# brd-relays3-draft2.net
KiCad netlist of a schematic drawn in EAGLE
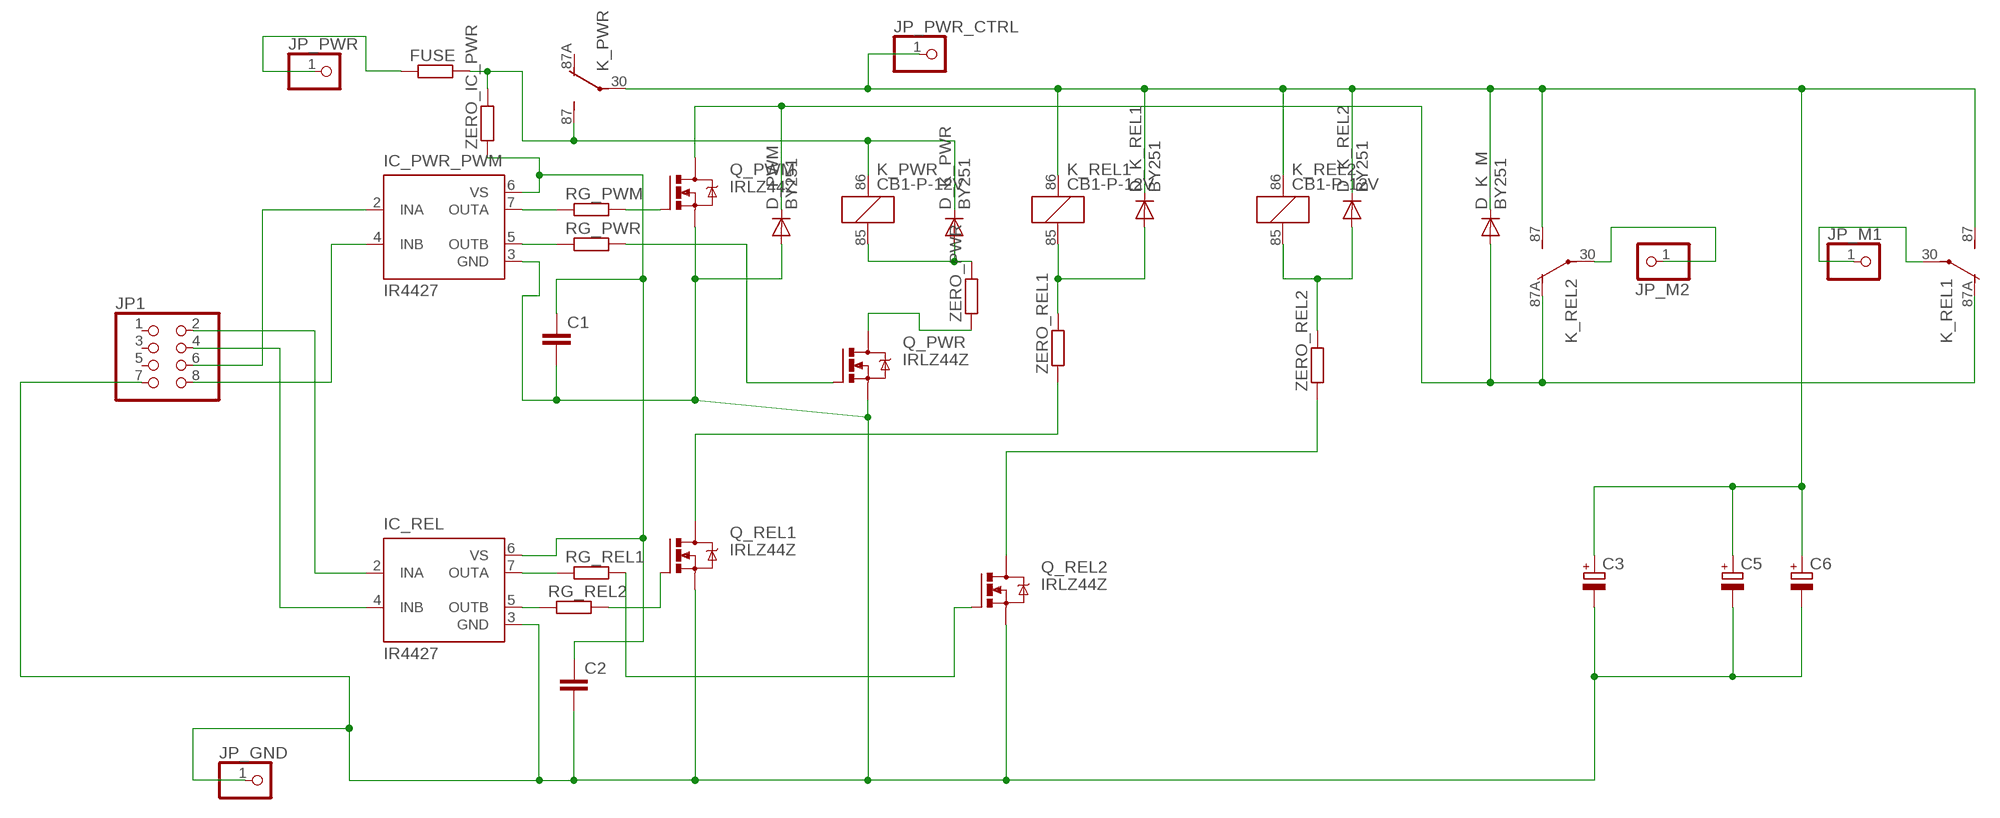
[diagram p0: schematic, sheet 1]

(export (version "E")
  (design (tool "Eeschema 10.0.6"))
  (components
    (comp (ref "C1")
      (value "C-EU050-055X075")
      (footprint "eagle-import:C050-055X075")
      (libsource (lib "eagle-import") (part "C-EU050-055X075"))
    )
    (comp (ref "C2")
      (value "C-EU050-055X075")
      (footprint "eagle-import:C050-055X075")
      (libsource (lib "eagle-import") (part "C-EU050-055X075"))
    )
    (comp (ref "C3")
      (value "CPOL-EUE5-13")
      (footprint "eagle-import:E5-13")
      (libsource (lib "eagle-import") (part "CPOL-EUE5-13"))
    )
    (comp (ref "C5")
      (value "CPOL-EUE5-13")
      (footprint "eagle-import:E5-13")
      (libsource (lib "eagle-import") (part "CPOL-EUE5-13"))
    )
    (comp (ref "C6")
      (value "CPOL-EUE5-13")
      (footprint "eagle-import:E5-13")
      (libsource (lib "eagle-import") (part "CPOL-EUE5-13"))
    )
    (comp (ref "D_K_M")
      (value "BY251")
      (footprint "eagle-import:DO201-15")
      (libsource (lib "eagle-import") (part "BY251"))
    )
    (comp (ref "D_K_PWR")
      (value "BY251")
      (footprint "eagle-import:DO201-15")
      (libsource (lib "eagle-import") (part "BY251"))
    )
    (comp (ref "D_K_REL1")
      (value "BY251")
      (footprint "eagle-import:DO201-15")
      (libsource (lib "eagle-import") (part "BY251"))
    )
    (comp (ref "D_K_REL2")
      (value "BY251")
      (footprint "eagle-import:DO201-15")
      (libsource (lib "eagle-import") (part "BY251"))
    )
    (comp (ref "D_PWM")
      (value "BY251")
      (footprint "eagle-import:DO201-15")
      (libsource (lib "eagle-import") (part "BY251"))
    )
    (comp (ref "FUSE")
      (value "R-EU_0207/10")
      (footprint "eagle-import:FUSE_PACK1")
      (libsource (lib "eagle-import") (part "R-EU_0207/10"))
    )
    (comp (ref "IC_PWR_PWM")
      (value "IR4427")
      (footprint "eagle-import:DIL08")
      (fields (field (name "MF") "INTERNATIONAL RECTIFIER(IR)"))
      (libsource (lib "eagle-import") (part "IR4427"))
    )
    (comp (ref "IC_REL")
      (value "IR4427")
      (footprint "eagle-import:DIL08")
      (fields (field (name "MF") "INTERNATIONAL RECTIFIER(IR)"))
      (libsource (lib "eagle-import") (part "IR4427"))
    )
    (comp (ref "JP1")
      (value "PINHD-2X4")
      (footprint "eagle-import:2X04")
      (libsource (lib "eagle-import") (part "PINHD-2X4"))
    )
    (comp (ref "JP_GND")
      (value "PINHD-1X1")
      (footprint "eagle-import:1X01")
      (libsource (lib "eagle-import") (part "PINHD-1X1"))
    )
    (comp (ref "JP_M1")
      (value "PINHD-1X1")
      (footprint "eagle-import:1X01")
      (libsource (lib "eagle-import") (part "PINHD-1X1"))
    )
    (comp (ref "JP_M2")
      (value "PINHD-1X1")
      (footprint "eagle-import:1X01")
      (libsource (lib "eagle-import") (part "PINHD-1X1"))
    )
    (comp (ref "JP_PWR")
      (value "PINHD-1X1")
      (footprint "eagle-import:1X01")
      (libsource (lib "eagle-import") (part "PINHD-1X1"))
    )
    (comp (ref "JP_PWR_CTRL")
      (value "PINHD-1X1")
      (footprint "eagle-import:1X01")
      (libsource (lib "eagle-import") (part "PINHD-1X1"))
    )
    (comp (ref "K_PWR")
      (value "CB1-P-12V")
      (footprint "eagle-import:CB1")
      (fields (field (name "MF") "AROMAT/ MATSUSHITA"))
      (libsource (lib "eagle-import") (part "CB1-P-12V"))
    )
    (comp (ref "K_REL1")
      (value "CB1-P-12V")
      (footprint "eagle-import:CB1")
      (fields (field (name "MF") "AROMAT/ MATSUSHITA"))
      (libsource (lib "eagle-import") (part "CB1-P-12V"))
    )
    (comp (ref "K_REL2")
      (value "CB1-P-12V")
      (footprint "eagle-import:CB1")
      (fields (field (name "MF") "AROMAT/ MATSUSHITA"))
      (libsource (lib "eagle-import") (part "CB1-P-12V"))
    )
    (comp (ref "Q_PWM")
      (value "IRLZ44Z")
      (footprint "eagle-import:TO220BH")
      (libsource (lib "eagle-import") (part "IRLZ44Z"))
    )
    (comp (ref "Q_PWR")
      (value "IRLZ44Z")
      (footprint "eagle-import:TO220BH")
      (libsource (lib "eagle-import") (part "IRLZ44Z"))
    )
    (comp (ref "Q_REL1")
      (value "IRLZ44Z")
      (footprint "eagle-import:TO220BH")
      (libsource (lib "eagle-import") (part "IRLZ44Z"))
    )
    (comp (ref "Q_REL2")
      (value "IRLZ44Z")
      (footprint "eagle-import:TO220BH")
      (libsource (lib "eagle-import") (part "IRLZ44Z"))
    )
    (comp (ref "RG_PWM")
      (value "R-EU_0207/10")
      (footprint "eagle-import:0207_10")
      (libsource (lib "eagle-import") (part "rcl_R-EU_0207/10"))
    )
    (comp (ref "RG_PWR")
      (value "R-EU_0207/10")
      (footprint "eagle-import:0207_10")
      (libsource (lib "eagle-import") (part "rcl_R-EU_0207/10"))
    )
    (comp (ref "RG_REL1")
      (value "R-EU_0207/10")
      (footprint "eagle-import:0207_10")
      (libsource (lib "eagle-import") (part "rcl_R-EU_0207/10"))
    )
    (comp (ref "RG_REL2")
      (value "R-EU_0207/10")
      (footprint "eagle-import:0207_10")
      (libsource (lib "eagle-import") (part "rcl_R-EU_0207/10"))
    )
    (comp (ref "ZERO_IC_PWR")
      (value "R-EU_0207/10")
      (footprint "eagle-import:0207_10")
      (libsource (lib "eagle-import") (part "rcl_R-EU_0207/10"))
    )
    (comp (ref "ZERO_PWR")
      (value "R-EU_0207/10")
      (footprint "eagle-import:0207_10")
      (libsource (lib "eagle-import") (part "rcl_R-EU_0207/10"))
    )
    (comp (ref "ZERO_REL1")
      (value "R-EU_0207/10")
      (footprint "eagle-import:0207_10")
      (libsource (lib "eagle-import") (part "rcl_R-EU_0207/10"))
    )
    (comp (ref "ZERO_REL2")
      (value "R-EU_0207/10")
      (footprint "eagle-import:0207_10")
      (libsource (lib "eagle-import") (part "rcl_R-EU_0207/10"))
    )
  )
  (nets
    (net (code "1") (name "Net-(FUSE-Pad1)") (class "Default")
      (node (ref "FUSE") (pin "1") (pinfunction "1_1") (pintype "passive"))
      (node (ref "JP_PWR") (pin "1") (pinfunction "1_1") (pintype "passive"))
    )
    (net (code "2") (name "Net-(IC_PWR_PWM-GND)") (class "Default")
      (node (ref "C1") (pin "2") (pinfunction "2_2") (pintype "passive"))
      (node (ref "C2") (pin "2") (pinfunction "2_2") (pintype "passive"))
      (node (ref "C3") (pin "-") (pinfunction "-_-") (pintype "passive"))
      (node (ref "C5") (pin "-") (pinfunction "-_-") (pintype "passive"))
      (node (ref "C6") (pin "-") (pinfunction "-_-") (pintype "passive"))
      (node (ref "D_PWM") (pin "A") (pinfunction "A_A") (pintype "passive"))
      (node (ref "IC_PWR_PWM") (pin "3") (pinfunction "GND_3") (pintype "power_in"))
      (node (ref "IC_REL") (pin "3") (pinfunction "GND_3") (pintype "power_in"))
      (node (ref "JP1") (pin "7") (pinfunction "7_7") (pintype "passive"))
      (node (ref "JP_GND") (pin "1") (pinfunction "1_1") (pintype "passive"))
      (node (ref "Q_PWM") (pin "S") (pinfunction "S_S") (pintype "passive"))
      (node (ref "Q_PWR") (pin "S") (pinfunction "S_S") (pintype "passive"))
      (node (ref "Q_REL1") (pin "S") (pinfunction "S_S") (pintype "passive"))
      (node (ref "Q_REL2") (pin "S") (pinfunction "S_S") (pintype "passive"))
    )
    (net (code "3") (name "Net-(IC_PWR_PWM-INA)") (class "Default")
      (node (ref "IC_PWR_PWM") (pin "2") (pinfunction "INA_2") (pintype "input"))
      (node (ref "JP1") (pin "6") (pinfunction "6_6") (pintype "passive"))
    )
    (net (code "4") (name "Net-(IC_PWR_PWM-INB)") (class "Default")
      (node (ref "IC_PWR_PWM") (pin "4") (pinfunction "INB_4") (pintype "input"))
      (node (ref "JP1") (pin "8") (pinfunction "8_8") (pintype "passive"))
    )
    (net (code "5") (name "Net-(IC_PWR_PWM-OUTA)") (class "Default")
      (node (ref "IC_PWR_PWM") (pin "7") (pinfunction "OUTA_7") (pintype "output"))
      (node (ref "RG_PWM") (pin "1") (pinfunction "1_1") (pintype "passive"))
    )
    (net (code "6") (name "Net-(IC_PWR_PWM-OUTB)") (class "Default")
      (node (ref "IC_PWR_PWM") (pin "5") (pinfunction "OUTB_5") (pintype "output"))
      (node (ref "RG_PWR") (pin "1") (pinfunction "1_1") (pintype "passive"))
    )
    (net (code "7") (name "Net-(IC_PWR_PWM-VS)") (class "Default")
      (node (ref "C1") (pin "1") (pinfunction "1_1") (pintype "passive"))
      (node (ref "C2") (pin "1") (pinfunction "1_1") (pintype "passive"))
      (node (ref "IC_PWR_PWM") (pin "6") (pinfunction "VS_6") (pintype "power_in"))
      (node (ref "IC_REL") (pin "6") (pinfunction "VS_6") (pintype "power_in"))
      (node (ref "ZERO_IC_PWR") (pin "1") (pinfunction "1_1") (pintype "passive"))
    )
    (net (code "8") (name "Net-(IC_REL-INA)") (class "Default")
      (node (ref "IC_REL") (pin "2") (pinfunction "INA_2") (pintype "input"))
      (node (ref "JP1") (pin "2") (pinfunction "2_2") (pintype "passive"))
    )
    (net (code "9") (name "Net-(IC_REL-INB)") (class "Default")
      (node (ref "IC_REL") (pin "4") (pinfunction "INB_4") (pintype "input"))
      (node (ref "JP1") (pin "4") (pinfunction "4_4") (pintype "passive"))
    )
    (net (code "10") (name "Net-(IC_REL-OUTA)") (class "Default")
      (node (ref "IC_REL") (pin "7") (pinfunction "OUTA_7") (pintype "output"))
      (node (ref "RG_REL1") (pin "1") (pinfunction "1_1") (pintype "passive"))
    )
    (net (code "11") (name "Net-(IC_REL-OUTB)") (class "Default")
      (node (ref "IC_REL") (pin "5") (pinfunction "OUTB_5") (pintype "output"))
      (node (ref "RG_REL2") (pin "1") (pinfunction "1_1") (pintype "passive"))
    )
    (net (code "12") (name "Net-(K_PWRA-1)") (class "Default")
      (node (ref "D_K_PWR") (pin "C") (pinfunction "C_C") (pintype "passive"))
      (node (ref "FUSE") (pin "2") (pinfunction "2_2") (pintype "passive"))
      (node (ref "K_PWR") (pin "86") (pinfunction "1_86") (pintype "passive"))
      (node (ref "K_PWR") (pin "87") (pinfunction "S_87") (pintype "passive"))
      (node (ref "ZERO_IC_PWR") (pin "2") (pinfunction "2_2") (pintype "passive"))
    )
    (net (code "13") (name "Net-(K_PWRA-2)") (class "Default")
      (node (ref "D_K_PWR") (pin "A") (pinfunction "A_A") (pintype "passive"))
      (node (ref "K_PWR") (pin "85") (pinfunction "2_85") (pintype "passive"))
      (node (ref "ZERO_PWR") (pin "2") (pinfunction "2_2") (pintype "passive"))
    )
    (net (code "14") (name "Net-(K_PWRB-P)") (class "Default")
      (node (ref "C3") (pin "+") (pinfunction "+_+") (pintype "passive"))
      (node (ref "C5") (pin "+") (pinfunction "+_+") (pintype "passive"))
      (node (ref "C6") (pin "+") (pinfunction "+_+") (pintype "passive"))
      (node (ref "D_K_M") (pin "C") (pinfunction "C_C") (pintype "passive"))
      (node (ref "D_K_REL1") (pin "C") (pinfunction "C_C") (pintype "passive"))
      (node (ref "D_K_REL2") (pin "C") (pinfunction "C_C") (pintype "passive"))
      (node (ref "JP_PWR_CTRL") (pin "1") (pinfunction "1_1") (pintype "passive"))
      (node (ref "K_PWR") (pin "30") (pinfunction "P_30") (pintype "passive"))
      (node (ref "K_REL1") (pin "86") (pinfunction "1_86") (pintype "passive"))
      (node (ref "K_REL1") (pin "87") (pinfunction "S_87") (pintype "passive"))
      (node (ref "K_REL2") (pin "86") (pinfunction "1_86") (pintype "passive"))
      (node (ref "K_REL2") (pin "87") (pinfunction "S_87") (pintype "passive"))
    )
    (net (code "15") (name "Net-(K_REL1A-2)") (class "Default")
      (node (ref "D_K_REL1") (pin "A") (pinfunction "A_A") (pintype "passive"))
      (node (ref "K_REL1") (pin "85") (pinfunction "2_85") (pintype "passive"))
      (node (ref "ZERO_REL1") (pin "2") (pinfunction "2_2") (pintype "passive"))
    )
    (net (code "16") (name "Net-(K_REL1B-O)") (class "Default")
      (node (ref "D_K_M") (pin "A") (pinfunction "A_A") (pintype "passive"))
      (node (ref "D_PWM") (pin "C") (pinfunction "C_C") (pintype "passive"))
      (node (ref "K_REL1") (pin "87A") (pinfunction "O_87A") (pintype "passive"))
      (node (ref "K_REL2") (pin "87A") (pinfunction "O_87A") (pintype "passive"))
      (node (ref "Q_PWM") (pin "D") (pinfunction "D_D") (pintype "passive"))
    )
    (net (code "17") (name "Net-(K_REL1B-P)") (class "Default")
      (node (ref "JP_M1") (pin "1") (pinfunction "1_1") (pintype "passive"))
      (node (ref "K_REL1") (pin "30") (pinfunction "P_30") (pintype "passive"))
    )
    (net (code "18") (name "Net-(K_REL2A-2)") (class "Default")
      (node (ref "D_K_REL2") (pin "A") (pinfunction "A_A") (pintype "passive"))
      (node (ref "K_REL2") (pin "85") (pinfunction "2_85") (pintype "passive"))
      (node (ref "ZERO_REL2") (pin "2") (pinfunction "2_2") (pintype "passive"))
    )
    (net (code "19") (name "Net-(K_REL2B-P)") (class "Default")
      (node (ref "JP_M2") (pin "1") (pinfunction "1_1") (pintype "passive"))
      (node (ref "K_REL2") (pin "30") (pinfunction "P_30") (pintype "passive"))
    )
    (net (code "20") (name "Net-(Q_PWM-PadG)") (class "Default")
      (node (ref "Q_PWM") (pin "G") (pinfunction "G_G") (pintype "passive"))
      (node (ref "RG_PWM") (pin "2") (pinfunction "2_2") (pintype "passive"))
    )
    (net (code "21") (name "Net-(Q_PWR-PadD)") (class "Default")
      (node (ref "Q_PWR") (pin "D") (pinfunction "D_D") (pintype "passive"))
      (node (ref "ZERO_PWR") (pin "1") (pinfunction "1_1") (pintype "passive"))
    )
    (net (code "22") (name "Net-(Q_PWR-PadG)") (class "Default")
      (node (ref "Q_PWR") (pin "G") (pinfunction "G_G") (pintype "passive"))
      (node (ref "RG_PWR") (pin "2") (pinfunction "2_2") (pintype "passive"))
    )
    (net (code "23") (name "Net-(Q_REL1-PadD)") (class "Default")
      (node (ref "Q_REL1") (pin "D") (pinfunction "D_D") (pintype "passive"))
      (node (ref "ZERO_REL1") (pin "1") (pinfunction "1_1") (pintype "passive"))
    )
    (net (code "24") (name "Net-(Q_REL1-PadG)") (class "Default")
      (node (ref "Q_REL1") (pin "G") (pinfunction "G_G") (pintype "passive"))
      (node (ref "RG_REL2") (pin "2") (pinfunction "2_2") (pintype "passive"))
    )
    (net (code "25") (name "Net-(Q_REL2-PadD)") (class "Default")
      (node (ref "Q_REL2") (pin "D") (pinfunction "D_D") (pintype "passive"))
      (node (ref "ZERO_REL2") (pin "1") (pinfunction "1_1") (pintype "passive"))
    )
    (net (code "26") (name "Net-(Q_REL2-PadG)") (class "Default")
      (node (ref "Q_REL2") (pin "G") (pinfunction "G_G") (pintype "passive"))
      (node (ref "RG_REL1") (pin "2") (pinfunction "2_2") (pintype "passive"))
    )
    (net (code "27") (name "unconnected-(JP1-Pad1)") (class "Default")
      (node (ref "JP1") (pin "1") (pinfunction "1_1") (pintype "passive"))
    )
    (net (code "28") (name "unconnected-(JP1-Pad3)") (class "Default")
      (node (ref "JP1") (pin "3") (pinfunction "3_3") (pintype "passive"))
    )
    (net (code "29") (name "unconnected-(JP1-Pad5)") (class "Default")
      (node (ref "JP1") (pin "5") (pinfunction "5_5") (pintype "passive"))
    )
    (net (code "30") (name "unconnected-(K_PWRB-O-Pad87A)") (class "Default")
      (node (ref "K_PWR") (pin "87A") (pinfunction "O_87A") (pintype "passive"))
    )
  )
)
